# slave_interface.net
KiCad netlist of a schematic drawn in Altium Designer
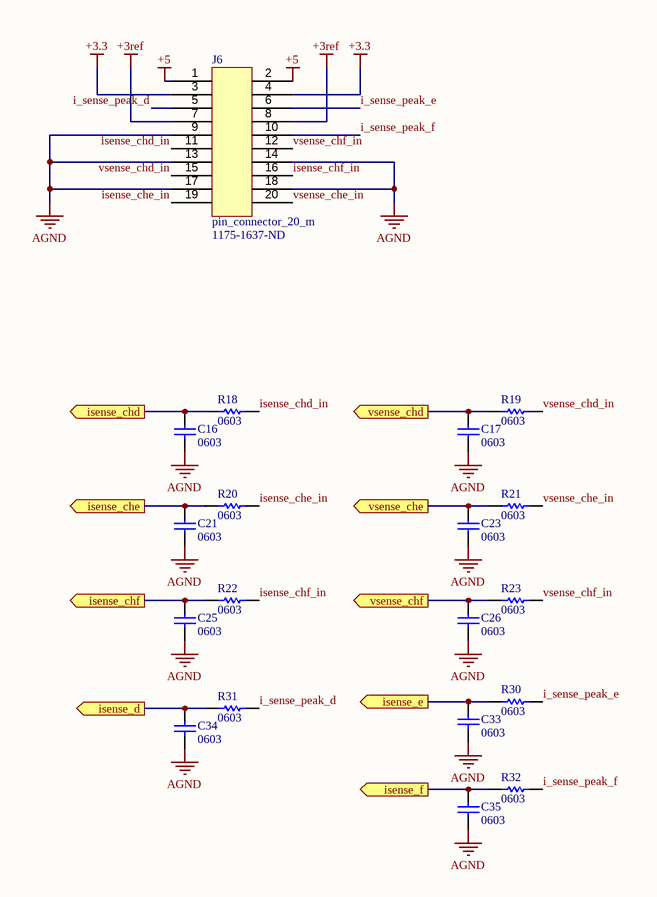
[diagram p0: slave_interface.SchDoc]

(export (version "E")
  (design (tool "Eeschema 10.0.6"))
  (components
    (comp (ref "C16")
      (value "0603")
      (footprint "CAP 0603_1608")
      (description "Capacitor")
      (fields (field (name "PUBLISHER") "Altium Limited"))
      (libsource (lib "Miscellaneous Devices") (part "Cap"))
    )
    (comp (ref "C17")
      (value "0603")
      (footprint "CAP 0603_1608")
      (description "Capacitor")
      (fields (field (name "PUBLISHER") "Altium Limited"))
      (libsource (lib "Miscellaneous Devices") (part "Cap"))
    )
    (comp (ref "C21")
      (value "0603")
      (footprint "CAP 0603_1608")
      (description "Capacitor")
      (fields (field (name "PUBLISHER") "Altium Limited"))
      (libsource (lib "Miscellaneous Devices") (part "Cap"))
    )
    (comp (ref "C23")
      (value "0603")
      (footprint "CAP 0603_1608")
      (description "Capacitor")
      (fields (field (name "PUBLISHER") "Altium Limited"))
      (libsource (lib "Miscellaneous Devices") (part "Cap"))
    )
    (comp (ref "C25")
      (value "0603")
      (footprint "CAP 0603_1608")
      (description "Capacitor")
      (fields (field (name "PUBLISHER") "Altium Limited"))
      (libsource (lib "Miscellaneous Devices") (part "Cap"))
    )
    (comp (ref "C26")
      (value "0603")
      (footprint "CAP 0603_1608")
      (description "Capacitor")
      (fields (field (name "PUBLISHER") "Altium Limited"))
      (libsource (lib "Miscellaneous Devices") (part "Cap"))
    )
    (comp (ref "C33")
      (value "0603")
      (footprint "CAP 0603_1608")
      (description "Capacitor")
      (fields (field (name "PUBLISHER") "Altium Limited"))
      (libsource (lib "Miscellaneous Devices") (part "Cap"))
    )
    (comp (ref "C34")
      (value "0603")
      (footprint "CAP 0603_1608")
      (description "Capacitor")
      (fields (field (name "PUBLISHER") "Altium Limited"))
      (libsource (lib "Miscellaneous Devices") (part "Cap"))
    )
    (comp (ref "C35")
      (value "0603")
      (footprint "CAP 0603_1608")
      (description "Capacitor")
      (fields (field (name "PUBLISHER") "Altium Limited"))
      (libsource (lib "Miscellaneous Devices") (part "Cap"))
    )
    (comp (ref "J6")
      (value "pin_connector_20_m")
      (footprint "PIN_20_MALE_3220-20-0300-00")
      (fields (field (name "SUPPLIER PART NUMBER 1") "1175-1637-ND"))
      (libsource (lib "coil_driver_lib") (part "pin_connector_20_m"))
    )
    (comp (ref "R18")
      (value "0603")
      (footprint "RES 0603_1608")
      (description "Resistor")
      (fields (field (name "PUBLISHER") "Altium Limited"))
      (libsource (lib "Miscellaneous Devices") (part "Res1"))
    )
    (comp (ref "R19")
      (value "0603")
      (footprint "RES 0603_1608")
      (description "Resistor")
      (fields (field (name "PUBLISHER") "Altium Limited"))
      (libsource (lib "Miscellaneous Devices") (part "Res1"))
    )
    (comp (ref "R20")
      (value "0603")
      (footprint "RES 0603_1608")
      (description "Resistor")
      (fields (field (name "PUBLISHER") "Altium Limited"))
      (libsource (lib "Miscellaneous Devices") (part "Res1"))
    )
    (comp (ref "R21")
      (value "0603")
      (footprint "RES 0603_1608")
      (description "Resistor")
      (fields (field (name "PUBLISHER") "Altium Limited"))
      (libsource (lib "Miscellaneous Devices") (part "Res1"))
    )
    (comp (ref "R22")
      (value "0603")
      (footprint "RES 0603_1608")
      (description "Resistor")
      (fields (field (name "PUBLISHER") "Altium Limited"))
      (libsource (lib "Miscellaneous Devices") (part "Res1"))
    )
    (comp (ref "R23")
      (value "0603")
      (footprint "RES 0603_1608")
      (description "Resistor")
      (fields (field (name "PUBLISHER") "Altium Limited"))
      (libsource (lib "Miscellaneous Devices") (part "Res1"))
    )
    (comp (ref "R30")
      (value "0603")
      (footprint "RES 0603_1608")
      (description "Resistor")
      (fields (field (name "PUBLISHER") "Altium Limited"))
      (libsource (lib "Miscellaneous Devices") (part "Res1"))
    )
    (comp (ref "R31")
      (value "0603")
      (footprint "RES 0603_1608")
      (description "Resistor")
      (fields (field (name "PUBLISHER") "Altium Limited"))
      (libsource (lib "Miscellaneous Devices") (part "Res1"))
    )
    (comp (ref "R32")
      (value "0603")
      (footprint "RES 0603_1608")
      (description "Resistor")
      (fields (field (name "PUBLISHER") "Altium Limited"))
      (libsource (lib "Miscellaneous Devices") (part "Res1"))
    )
  )
  (nets
    (net (code "1") (name "+3.3") (class "Default")
      (node (ref "J6") (pin "3") (pintype "passive"))
      (node (ref "J6") (pin "4") (pintype "passive"))
    )
    (net (code "2") (name "+3ref") (class "Default")
      (node (ref "J6") (pin "7") (pintype "passive"))
      (node (ref "J6") (pin "8") (pintype "passive"))
    )
    (net (code "3") (name "+5") (class "Default")
      (node (ref "J6") (pin "1") (pintype "passive"))
      (node (ref "J6") (pin "2") (pintype "passive"))
    )
    (net (code "4") (name "/i_sense_peak_d") (class "Default")
      (node (ref "J6") (pin "5") (pintype "passive"))
      (node (ref "R31") (pin "2") (pinfunction "2_2") (pintype "passive"))
    )
    (net (code "5") (name "/i_sense_peak_e") (class "Default")
      (node (ref "J6") (pin "6") (pintype "passive"))
      (node (ref "R30") (pin "2") (pinfunction "2_2") (pintype "passive"))
    )
    (net (code "6") (name "/i_sense_peak_f") (class "Default")
      (node (ref "J6") (pin "10") (pintype "passive"))
      (node (ref "R32") (pin "2") (pinfunction "2_2") (pintype "passive"))
    )
    (net (code "7") (name "/isense_chd") (class "Default")
      (node (ref "C16") (pin "2") (pinfunction "2_2") (pintype "passive"))
      (node (ref "R18") (pin "1") (pinfunction "1_1") (pintype "passive"))
    )
    (net (code "8") (name "/isense_chd_in") (class "Default")
      (node (ref "J6") (pin "11") (pintype "passive"))
      (node (ref "R18") (pin "2") (pinfunction "2_2") (pintype "passive"))
    )
    (net (code "9") (name "/isense_che") (class "Default")
      (node (ref "C21") (pin "2") (pinfunction "2_2") (pintype "passive"))
      (node (ref "R20") (pin "1") (pinfunction "1_1") (pintype "passive"))
    )
    (net (code "10") (name "/isense_che_in") (class "Default")
      (node (ref "J6") (pin "19") (pintype "passive"))
      (node (ref "R20") (pin "2") (pinfunction "2_2") (pintype "passive"))
    )
    (net (code "11") (name "/isense_chf") (class "Default")
      (node (ref "C25") (pin "2") (pinfunction "2_2") (pintype "passive"))
      (node (ref "R22") (pin "1") (pinfunction "1_1") (pintype "passive"))
    )
    (net (code "12") (name "/isense_chf_in") (class "Default")
      (node (ref "J6") (pin "16") (pintype "passive"))
      (node (ref "R22") (pin "2") (pinfunction "2_2") (pintype "passive"))
    )
    (net (code "13") (name "/isense_d") (class "Default")
      (node (ref "C34") (pin "2") (pinfunction "2_2") (pintype "passive"))
      (node (ref "R31") (pin "1") (pinfunction "1_1") (pintype "passive"))
    )
    (net (code "14") (name "/isense_e") (class "Default")
      (node (ref "C33") (pin "2") (pinfunction "2_2") (pintype "passive"))
      (node (ref "R30") (pin "1") (pinfunction "1_1") (pintype "passive"))
    )
    (net (code "15") (name "/isense_f") (class "Default")
      (node (ref "C35") (pin "2") (pinfunction "2_2") (pintype "passive"))
      (node (ref "R32") (pin "1") (pinfunction "1_1") (pintype "passive"))
    )
    (net (code "16") (name "/vsense_chd") (class "Default")
      (node (ref "C17") (pin "2") (pinfunction "2_2") (pintype "passive"))
      (node (ref "R19") (pin "1") (pinfunction "1_1") (pintype "passive"))
    )
    (net (code "17") (name "/vsense_chd_in") (class "Default")
      (node (ref "J6") (pin "15") (pintype "passive"))
      (node (ref "R19") (pin "2") (pinfunction "2_2") (pintype "passive"))
    )
    (net (code "18") (name "/vsense_che") (class "Default")
      (node (ref "C23") (pin "2") (pinfunction "2_2") (pintype "passive"))
      (node (ref "R21") (pin "1") (pinfunction "1_1") (pintype "passive"))
    )
    (net (code "19") (name "/vsense_che_in") (class "Default")
      (node (ref "J6") (pin "20") (pintype "passive"))
      (node (ref "R21") (pin "2") (pinfunction "2_2") (pintype "passive"))
    )
    (net (code "20") (name "/vsense_chf") (class "Default")
      (node (ref "C26") (pin "2") (pinfunction "2_2") (pintype "passive"))
      (node (ref "R23") (pin "1") (pinfunction "1_1") (pintype "passive"))
    )
    (net (code "21") (name "/vsense_chf_in") (class "Default")
      (node (ref "J6") (pin "12") (pintype "passive"))
      (node (ref "R23") (pin "2") (pinfunction "2_2") (pintype "passive"))
    )
    (net (code "22") (name "AGND") (class "Default")
      (node (ref "C16") (pin "1") (pinfunction "1_1") (pintype "passive"))
      (node (ref "C17") (pin "1") (pinfunction "1_1") (pintype "passive"))
      (node (ref "C21") (pin "1") (pinfunction "1_1") (pintype "passive"))
      (node (ref "C23") (pin "1") (pinfunction "1_1") (pintype "passive"))
      (node (ref "C25") (pin "1") (pinfunction "1_1") (pintype "passive"))
      (node (ref "C26") (pin "1") (pinfunction "1_1") (pintype "passive"))
      (node (ref "C33") (pin "1") (pinfunction "1_1") (pintype "passive"))
      (node (ref "C34") (pin "1") (pinfunction "1_1") (pintype "passive"))
      (node (ref "C35") (pin "1") (pinfunction "1_1") (pintype "passive"))
      (node (ref "J6") (pin "13") (pintype "passive"))
      (node (ref "J6") (pin "14") (pintype "passive"))
      (node (ref "J6") (pin "17") (pintype "passive"))
      (node (ref "J6") (pin "18") (pintype "passive"))
      (node (ref "J6") (pin "9") (pintype "passive"))
    )
  )
)
